# 2_main_mcu.net
KiCad netlist of a schematic drawn in Altium Designer
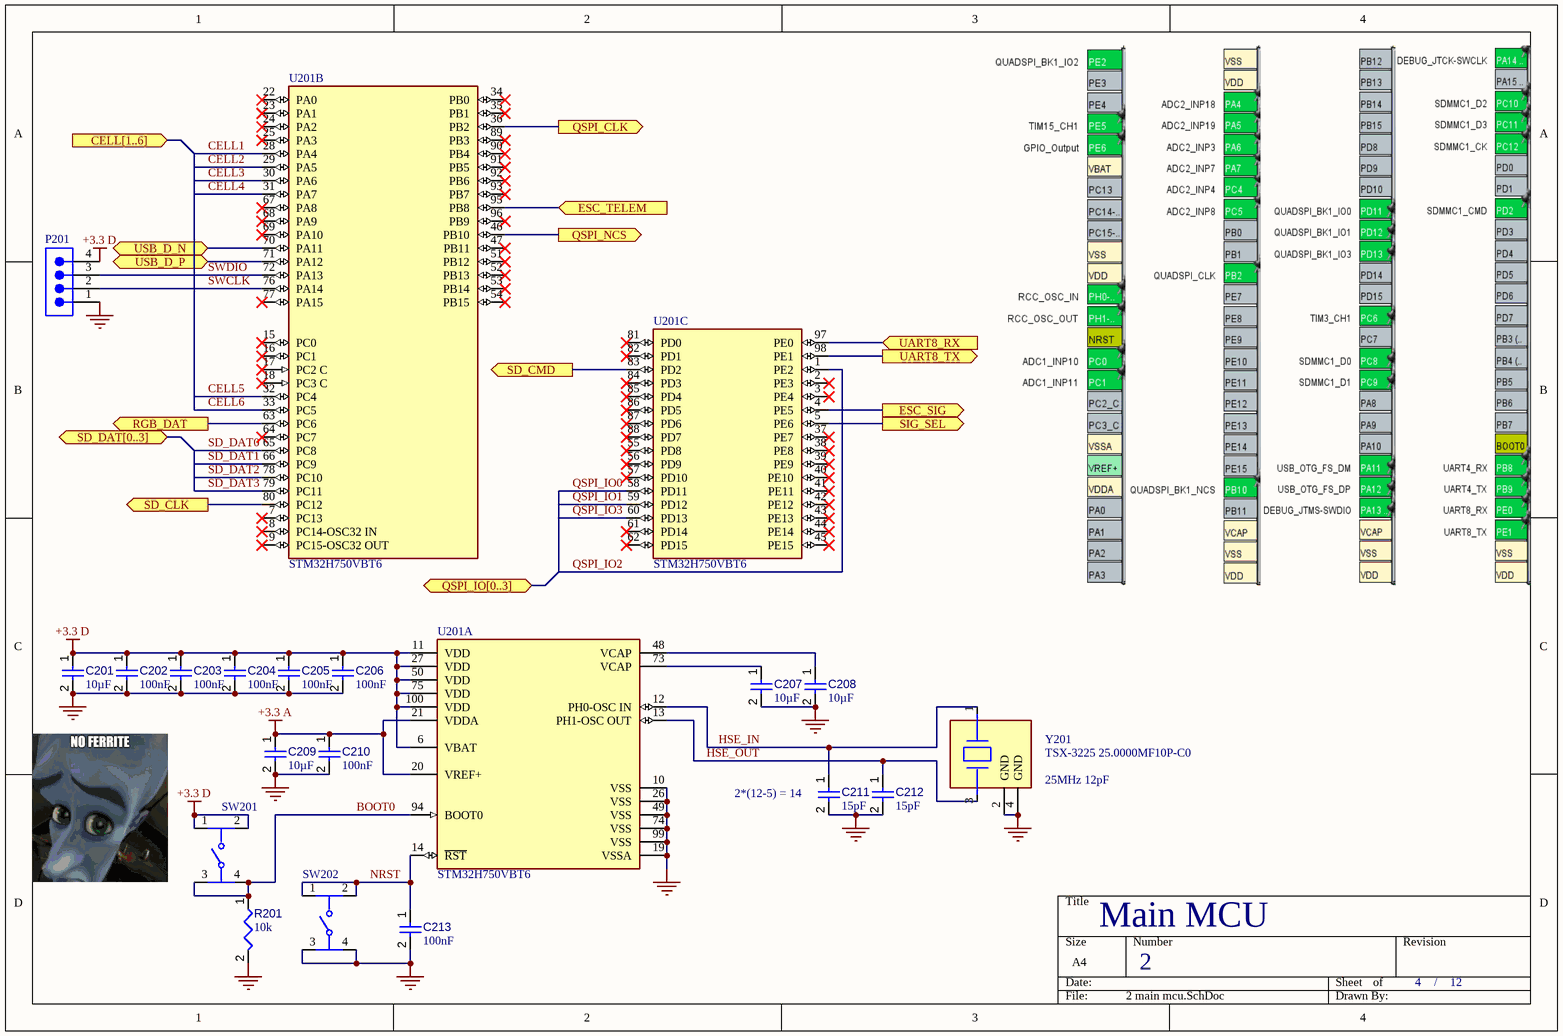
[diagram p0: 2 main mcu.SchDoc]

(export (version "E")
  (design (tool "Eeschema 10.0.6"))
  (components
    (comp (ref "C201")
      (value "10µF")
      (footprint "CAPC0603(1608)100_L")
      (description "Chip Capacitor, 10µF +/-20%, 10V, 0603, Thickness 1 mm")
      (fields (field (name "TOLERANCE") "10%") (field (name "Comment") "Capacitor 10µF +/-20% 10V 0603"))
      (libsource (lib "UBC Uncrewed Aircraft Systems") (part "CAP-NP-2"))
    )
    (comp (ref "C202")
      (value "100nF")
      (footprint "CAPC0402(1005)60_L")
      (description "Chip Capacitor, 100nF +/-20%, 25V, 0402, Thickness 0.6 mm")
      (fields (field (name "TOLERANCE") "10%") (field (name "Comment") "Capacitor 100nF +/-20% 25V 0402"))
      (libsource (lib "UBC Uncrewed Aircraft Systems") (part "CAP-NP-2"))
    )
    (comp (ref "C203")
      (value "100nF")
      (footprint "CAPC0402(1005)60_L")
      (description "Chip Capacitor, 100nF +/-20%, 25V, 0402, Thickness 0.6 mm")
      (fields (field (name "TOLERANCE") "10%") (field (name "Comment") "Capacitor 100nF +/-20% 25V 0402"))
      (libsource (lib "UBC Uncrewed Aircraft Systems") (part "CAP-NP-2"))
    )
    (comp (ref "C204")
      (value "100nF")
      (footprint "CAPC0402(1005)60_L")
      (description "Chip Capacitor, 100nF +/-20%, 25V, 0402, Thickness 0.6 mm")
      (fields (field (name "TOLERANCE") "10%") (field (name "Comment") "Capacitor 100nF +/-20% 25V 0402"))
      (libsource (lib "UBC Uncrewed Aircraft Systems") (part "CAP-NP-2"))
    )
    (comp (ref "C205")
      (value "100nF")
      (footprint "CAPC0402(1005)60_L")
      (description "Chip Capacitor, 100nF +/-20%, 25V, 0402, Thickness 0.6 mm")
      (fields (field (name "TOLERANCE") "10%") (field (name "Comment") "Capacitor 100nF +/-20% 25V 0402"))
      (libsource (lib "UBC Uncrewed Aircraft Systems") (part "CAP-NP-2"))
    )
    (comp (ref "C206")
      (value "100nF")
      (footprint "CAPC0402(1005)60_L")
      (description "Chip Capacitor, 100nF +/-20%, 25V, 0402, Thickness 0.6 mm")
      (fields (field (name "TOLERANCE") "10%") (field (name "Comment") "Capacitor 100nF +/-20% 25V 0402"))
      (libsource (lib "UBC Uncrewed Aircraft Systems") (part "CAP-NP-2"))
    )
    (comp (ref "C207")
      (value "10µF")
      (footprint "CAPC0603(1608)100_L")
      (description "Chip Capacitor, 10µF +/-20%, 10V, 0603, Thickness 1 mm")
      (fields (field (name "TOLERANCE") "10%") (field (name "Comment") "Capacitor 10µF +/-20% 10V 0603"))
      (libsource (lib "UBC Uncrewed Aircraft Systems") (part "CAP-NP-2"))
    )
    (comp (ref "C208")
      (value "10µF")
      (footprint "CAPC0603(1608)100_L")
      (description "Chip Capacitor, 10µF +/-20%, 10V, 0603, Thickness 1 mm")
      (fields (field (name "TOLERANCE") "10%") (field (name "Comment") "Capacitor 10µF +/-20% 10V 0603"))
      (libsource (lib "UBC Uncrewed Aircraft Systems") (part "CAP-NP-2"))
    )
    (comp (ref "C209")
      (value "10µF")
      (footprint "CAPC0603(1608)100_L")
      (description "Chip Capacitor, 10µF +/-20%, 10V, 0603, Thickness 1 mm")
      (fields (field (name "TOLERANCE") "10%") (field (name "Comment") "Capacitor 10µF +/-20% 10V 0603"))
      (libsource (lib "UBC Uncrewed Aircraft Systems") (part "CAP-NP-2"))
    )
    (comp (ref "C210")
      (value "100nF")
      (footprint "CAPC0402(1005)60_L")
      (description "Chip Capacitor, 100nF +/-20%, 25V, 0402, Thickness 0.6 mm")
      (fields (field (name "TOLERANCE") "10%") (field (name "Comment") "Capacitor 100nF +/-20% 25V 0402"))
      (libsource (lib "UBC Uncrewed Aircraft Systems") (part "CAP-NP-2"))
    )
    (comp (ref "C211")
      (value "15pF")
      (footprint "CAPC0402(1005)60_L")
      (description "Chip Capacitor, 15pF +/-20%, 50V, 0402, Thickness 0.6 mm")
      (fields (field (name "TOLERANCE") "5%") (field (name "JLCPCB PART #") "C1548"))
      (libsource (lib "UBC Uncrewed Aircraft Systems") (part "CAP-NP-2"))
    )
    (comp (ref "C212")
      (value "15pF")
      (footprint "CAPC0402(1005)60_L")
      (description "Chip Capacitor, 15pF +/-20%, 50V, 0402, Thickness 0.6 mm")
      (fields (field (name "TOLERANCE") "5%") (field (name "JLCPCB PART #") "C1548"))
      (libsource (lib "UBC Uncrewed Aircraft Systems") (part "CAP-NP-2"))
    )
    (comp (ref "C213")
      (value "100nF")
      (footprint "CAPC0402(1005)60_L")
      (description "Chip Capacitor, 100nF +/-20%, 25V, 0402, Thickness 0.6 mm")
      (fields (field (name "TOLERANCE") "10%") (field (name "Comment") "Capacitor 100nF +/-20% 25V 0402"))
      (libsource (lib "UBC Uncrewed Aircraft Systems") (part "CAP-NP-2"))
    )
    (comp (ref "P201")
      (value "61300411121")
      (footprint "61300411121")
      (libsource (lib "Altium Content Vault") (part "Header_Male_1R_04P"))
    )
    (comp (ref "R201")
      (value "10k")
      (footprint "RESC0402(1005)_L")
      (description "Chip Resistor, 10 kOhms, +/-1 %, 63 mW, -55 to 125 degC, 0402")
      (fields (field (name "POWER") "63mW") (field (name "TOLERANCE") "1%"))
      (libsource (lib "UBC Uncrewed Aircraft Systems") (part "RES-2"))
    )
    (comp (ref "SW201")
      (value "PTS810SJM250SMTRLFS")
      (footprint "FP-PTS810SJM250SMTRLFS-MFG")
      (description "SWITCH TACTILE SPST-NO 0.05A 16V")
      (libsource (lib "Altium Content Vault") (part "1adf0dd01260c80cf25a44bfd6b99ba"))
    )
    (comp (ref "SW202")
      (value "PTS810SJM250SMTRLFS")
      (footprint "FP-PTS810SJM250SMTRLFS-MFG")
      (description "SWITCH TACTILE SPST-NO 0.05A 16V")
      (libsource (lib "Altium Content Vault") (part "1adf0dd01260c80cf25a44bfd6b99ba"))
    )
    (comp (ref "U201")
      (value "STM32H750VBT6")
      (footprint "FP-LQFP100-1L-MFG")
      (description "IC MCU 32BIT 128KB FLASH 100LQFP")
      (fields
        (field (name "OCTOPART") "https://octopart.com/stm32h750vbt6-stmicroelectronics-94048547")
        (field (name "MANUFACTURER") "STMicroelectronics")
      )
      (libsource (lib "Altium Content Vault") (part "aca449acb2b80670ba40d015d68dc7a"))
    )
    (comp (ref "Y201")
      (value "TSX-3225 25.0000MF10P-C0")
      (footprint "FP-TSX-3225-MFG")
      (description "CRYSTAL 25.0000MHZ 18PF SMD")
      (libsource (lib "Altium Content Vault") (part "927a1cf76fcef45674bd853ccf050d4"))
    )
  )
  (nets
    (net (code "1") (name "+3.3 A") (class "Default")
      (node (ref "C209") (pin "1") (pinfunction "1_1") (pintype "passive"))
      (node (ref "C210") (pin "1") (pinfunction "1_1") (pintype "passive"))
      (node (ref "U201") (pin "20") (pinfunction "VREF+_20") (pintype "power_in"))
      (node (ref "U201") (pin "21") (pinfunction "VDDA_21") (pintype "power_in"))
    )
    (net (code "2") (name "+3.3 D") (class "Default")
      (node (ref "C201") (pin "1") (pinfunction "1_1") (pintype "passive"))
      (node (ref "C202") (pin "1") (pinfunction "1_1") (pintype "passive"))
      (node (ref "C203") (pin "1") (pinfunction "1_1") (pintype "passive"))
      (node (ref "C204") (pin "1") (pinfunction "1_1") (pintype "passive"))
      (node (ref "C205") (pin "1") (pinfunction "1_1") (pintype "passive"))
      (node (ref "C206") (pin "1") (pinfunction "1_1") (pintype "passive"))
      (node (ref "P201") (pin "4") (pinfunction "4_4") (pintype "passive"))
      (node (ref "SW201") (pin "1") (pinfunction "1_1") (pintype "passive"))
      (node (ref "SW201") (pin "2") (pinfunction "2_2") (pintype "passive"))
      (node (ref "U201") (pin "100") (pinfunction "VDD_100") (pintype "power_in"))
      (node (ref "U201") (pin "11") (pinfunction "VDD_11") (pintype "power_in"))
      (node (ref "U201") (pin "27") (pinfunction "VDD_27") (pintype "power_in"))
      (node (ref "U201") (pin "50") (pinfunction "VDD_50") (pintype "power_in"))
      (node (ref "U201") (pin "6") (pinfunction "VBAT_6") (pintype "power_in"))
      (node (ref "U201") (pin "75") (pinfunction "VDD_75") (pintype "power_in"))
    )
    (net (code "3") (name "/BOOT0") (class "Default")
      (node (ref "R201") (pin "1") (pinfunction "1_1") (pintype "passive"))
      (node (ref "SW201") (pin "3") (pinfunction "3_3") (pintype "passive"))
      (node (ref "SW201") (pin "4") (pinfunction "4_4") (pintype "passive"))
      (node (ref "U201") (pin "94") (pinfunction "BOOT0_94") (pintype "input"))
    )
    (net (code "4") (name "/CELL1") (class "Default")
      (node (ref "U201") (pin "28") (pinfunction "PA4_28") (pintype "bidirectional"))
    )
    (net (code "5") (name "/CELL2") (class "Default")
      (node (ref "U201") (pin "29") (pinfunction "PA5_29") (pintype "bidirectional"))
    )
    (net (code "6") (name "/CELL3") (class "Default")
      (node (ref "U201") (pin "30") (pinfunction "PA6_30") (pintype "bidirectional"))
    )
    (net (code "7") (name "/CELL4") (class "Default")
      (node (ref "U201") (pin "31") (pinfunction "PA7_31") (pintype "bidirectional"))
    )
    (net (code "8") (name "/CELL5") (class "Default")
      (node (ref "U201") (pin "32") (pinfunction "PC4_32") (pintype "bidirectional"))
    )
    (net (code "9") (name "/CELL6") (class "Default")
      (node (ref "U201") (pin "33") (pinfunction "PC5_33") (pintype "bidirectional"))
    )
    (net (code "11") (name "/ESC_SIG") (class "Default")
      (node (ref "U201") (pin "4") (pinfunction "PE5_4") (pintype "bidirectional"))
    )
    (net (code "12") (name "/ESC_TELEM") (class "Default")
      (node (ref "U201") (pin "95") (pinfunction "PB8_95") (pintype "bidirectional"))
    )
    (net (code "13") (name "/HSE_IN") (class "Default")
      (node (ref "C211") (pin "1") (pinfunction "1_1") (pintype "passive"))
      (node (ref "U201") (pin "12") (pinfunction "PH0-OSC_IN_12") (pintype "bidirectional"))
      (node (ref "Y201") (pin "1") (pinfunction "1_1") (pintype "passive"))
    )
    (net (code "14") (name "/HSE_OUT") (class "Default")
      (node (ref "C212") (pin "1") (pinfunction "1_1") (pintype "passive"))
      (node (ref "U201") (pin "13") (pinfunction "PH1-OSC_OUT_13") (pintype "bidirectional"))
      (node (ref "Y201") (pin "3") (pinfunction "3_3") (pintype "passive"))
    )
    (net (code "15") (name "/NRST") (class "Default")
      (node (ref "C213") (pin "1") (pinfunction "1_1") (pintype "passive"))
      (node (ref "SW202") (pin "1") (pinfunction "1_1") (pintype "passive"))
      (node (ref "SW202") (pin "2") (pinfunction "2_2") (pintype "passive"))
      (node (ref "U201") (pin "14") (pinfunction "~{RST}_14") (pintype "bidirectional"))
    )
    (net (code "16") (name "/QSPI_CLK") (class "Default")
      (node (ref "U201") (pin "36") (pinfunction "PB2_36") (pintype "bidirectional"))
    )
    (net (code "17") (name "/QSPI_IO0") (class "Default")
      (node (ref "U201") (pin "58") (pinfunction "PD11_58") (pintype "bidirectional"))
    )
    (net (code "18") (name "/QSPI_IO1") (class "Default")
      (node (ref "U201") (pin "59") (pinfunction "PD12_59") (pintype "bidirectional"))
    )
    (net (code "19") (name "/QSPI_IO2") (class "Default")
      (node (ref "U201") (pin "1") (pinfunction "PE2_1") (pintype "bidirectional"))
    )
    (net (code "20") (name "/QSPI_IO3") (class "Default")
      (node (ref "U201") (pin "60") (pinfunction "PD13_60") (pintype "bidirectional"))
    )
    (net (code "22") (name "/QSPI_NCS") (class "Default")
      (node (ref "U201") (pin "46") (pinfunction "PB10_46") (pintype "bidirectional"))
    )
    (net (code "23") (name "/RGB_DAT") (class "Default")
      (node (ref "U201") (pin "63") (pinfunction "PC6_63") (pintype "bidirectional"))
    )
    (net (code "24") (name "/SD_CLK") (class "Default")
      (node (ref "U201") (pin "80") (pinfunction "PC12_80") (pintype "bidirectional"))
    )
    (net (code "25") (name "/SD_CMD") (class "Default")
      (node (ref "U201") (pin "83") (pinfunction "PD2_83") (pintype "bidirectional"))
    )
    (net (code "26") (name "/SD_DAT0") (class "Default")
      (node (ref "U201") (pin "65") (pinfunction "PC8_65") (pintype "bidirectional"))
    )
    (net (code "27") (name "/SD_DAT1") (class "Default")
      (node (ref "U201") (pin "66") (pinfunction "PC9_66") (pintype "bidirectional"))
    )
    (net (code "28") (name "/SD_DAT2") (class "Default")
      (node (ref "U201") (pin "78") (pinfunction "PC10_78") (pintype "bidirectional"))
    )
    (net (code "29") (name "/SD_DAT3") (class "Default")
      (node (ref "U201") (pin "79") (pinfunction "PC11_79") (pintype "bidirectional"))
    )
    (net (code "31") (name "/SIG_SEL") (class "Default")
      (node (ref "U201") (pin "5") (pinfunction "PE6_5") (pintype "bidirectional"))
    )
    (net (code "32") (name "/SWCLK") (class "Default")
      (node (ref "P201") (pin "2") (pinfunction "2_2") (pintype "passive"))
      (node (ref "U201") (pin "76") (pinfunction "PA14_76") (pintype "bidirectional"))
    )
    (net (code "33") (name "/SWDIO") (class "Default")
      (node (ref "P201") (pin "3") (pinfunction "3_3") (pintype "passive"))
      (node (ref "U201") (pin "72") (pinfunction "PA13_72") (pintype "bidirectional"))
    )
    (net (code "34") (name "/UART8_RX") (class "Default")
      (node (ref "U201") (pin "97") (pinfunction "PE0_97") (pintype "bidirectional"))
    )
    (net (code "35") (name "/UART8_TX") (class "Default")
      (node (ref "U201") (pin "98") (pinfunction "PE1_98") (pintype "bidirectional"))
    )
    (net (code "36") (name "/USB_D_N") (class "Default")
      (node (ref "U201") (pin "70") (pinfunction "PA11_70") (pintype "bidirectional"))
    )
    (net (code "37") (name "/USB_D_P") (class "Default")
      (node (ref "U201") (pin "71") (pinfunction "PA12_71") (pintype "bidirectional"))
    )
    (net (code "38") (name "GND") (class "Default")
      (node (ref "C201") (pin "2") (pinfunction "2_2") (pintype "passive"))
      (node (ref "C202") (pin "2") (pinfunction "2_2") (pintype "passive"))
      (node (ref "C203") (pin "2") (pinfunction "2_2") (pintype "passive"))
      (node (ref "C204") (pin "2") (pinfunction "2_2") (pintype "passive"))
      (node (ref "C205") (pin "2") (pinfunction "2_2") (pintype "passive"))
      (node (ref "C206") (pin "2") (pinfunction "2_2") (pintype "passive"))
      (node (ref "C207") (pin "2") (pinfunction "2_2") (pintype "passive"))
      (node (ref "C208") (pin "2") (pinfunction "2_2") (pintype "passive"))
      (node (ref "C209") (pin "2") (pinfunction "2_2") (pintype "passive"))
      (node (ref "C210") (pin "2") (pinfunction "2_2") (pintype "passive"))
      (node (ref "C211") (pin "2") (pinfunction "2_2") (pintype "passive"))
      (node (ref "C212") (pin "2") (pinfunction "2_2") (pintype "passive"))
      (node (ref "C213") (pin "2") (pinfunction "2_2") (pintype "passive"))
      (node (ref "P201") (pin "1") (pinfunction "1_1") (pintype "passive"))
      (node (ref "R201") (pin "2") (pinfunction "2_2") (pintype "passive"))
      (node (ref "SW202") (pin "3") (pinfunction "3_3") (pintype "passive"))
      (node (ref "SW202") (pin "4") (pinfunction "4_4") (pintype "passive"))
      (node (ref "U201") (pin "10") (pinfunction "VSS_10") (pintype "power_in"))
      (node (ref "U201") (pin "19") (pinfunction "VSSA_19") (pintype "power_in"))
      (node (ref "U201") (pin "26") (pinfunction "VSS_26") (pintype "power_in"))
      (node (ref "U201") (pin "49") (pinfunction "VSS_49") (pintype "power_in"))
      (node (ref "U201") (pin "74") (pinfunction "VSS_74") (pintype "power_in"))
      (node (ref "U201") (pin "99") (pinfunction "VSS_99") (pintype "power_in"))
      (node (ref "Y201") (pin "2") (pinfunction "GND_2") (pintype "power_in"))
      (node (ref "Y201") (pin "4") (pinfunction "GND_4") (pintype "power_in"))
    )
    (net (code "39") (name "Net-(C207-Pad1)") (class "Default")
      (node (ref "C207") (pin "1") (pinfunction "1_1") (pintype "passive"))
      (node (ref "U201") (pin "73") (pinfunction "VCAP_73") (pintype "power_in"))
    )
    (net (code "40") (name "Net-(C208-Pad1)") (class "Default")
      (node (ref "C208") (pin "1") (pinfunction "1_1") (pintype "passive"))
      (node (ref "U201") (pin "48") (pinfunction "VCAP_48") (pintype "power_in"))
    )
    (net (code "41") (name "unconnected-(U201B-PA0-Pad22)") (class "Default")
      (node (ref "U201") (pin "22") (pinfunction "PA0_22") (pintype "bidirectional+no_connect"))
    )
    (net (code "42") (name "unconnected-(U201B-PA1-Pad23)") (class "Default")
      (node (ref "U201") (pin "23") (pinfunction "PA1_23") (pintype "bidirectional+no_connect"))
    )
    (net (code "43") (name "unconnected-(U201B-PA2-Pad24)") (class "Default")
      (node (ref "U201") (pin "24") (pinfunction "PA2_24") (pintype "bidirectional+no_connect"))
    )
    (net (code "44") (name "unconnected-(U201B-PA3-Pad25)") (class "Default")
      (node (ref "U201") (pin "25") (pinfunction "PA3_25") (pintype "bidirectional+no_connect"))
    )
    (net (code "45") (name "unconnected-(U201B-PA8-Pad67)") (class "Default")
      (node (ref "U201") (pin "67") (pinfunction "PA8_67") (pintype "bidirectional+no_connect"))
    )
    (net (code "46") (name "unconnected-(U201B-PA9-Pad68)") (class "Default")
      (node (ref "U201") (pin "68") (pinfunction "PA9_68") (pintype "bidirectional+no_connect"))
    )
    (net (code "47") (name "unconnected-(U201B-PA10-Pad69)") (class "Default")
      (node (ref "U201") (pin "69") (pinfunction "PA10_69") (pintype "bidirectional+no_connect"))
    )
    (net (code "48") (name "unconnected-(U201B-PA15-Pad77)") (class "Default")
      (node (ref "U201") (pin "77") (pinfunction "PA15_77") (pintype "bidirectional+no_connect"))
    )
    (net (code "49") (name "unconnected-(U201B-PB0-Pad34)") (class "Default")
      (node (ref "U201") (pin "34") (pinfunction "PB0_34") (pintype "bidirectional+no_connect"))
    )
    (net (code "50") (name "unconnected-(U201B-PB1-Pad35)") (class "Default")
      (node (ref "U201") (pin "35") (pinfunction "PB1_35") (pintype "bidirectional+no_connect"))
    )
    (net (code "51") (name "unconnected-(U201B-PB3-Pad89)") (class "Default")
      (node (ref "U201") (pin "89") (pinfunction "PB3_89") (pintype "bidirectional+no_connect"))
    )
    (net (code "52") (name "unconnected-(U201B-PB4-Pad90)") (class "Default")
      (node (ref "U201") (pin "90") (pinfunction "PB4_90") (pintype "bidirectional+no_connect"))
    )
    (net (code "53") (name "unconnected-(U201B-PB5-Pad91)") (class "Default")
      (node (ref "U201") (pin "91") (pinfunction "PB5_91") (pintype "bidirectional+no_connect"))
    )
    (net (code "54") (name "unconnected-(U201B-PB6-Pad92)") (class "Default")
      (node (ref "U201") (pin "92") (pinfunction "PB6_92") (pintype "bidirectional+no_connect"))
    )
    (net (code "55") (name "unconnected-(U201B-PB7-Pad93)") (class "Default")
      (node (ref "U201") (pin "93") (pinfunction "PB7_93") (pintype "bidirectional+no_connect"))
    )
    (net (code "56") (name "unconnected-(U201B-PB9-Pad96)") (class "Default")
      (node (ref "U201") (pin "96") (pinfunction "PB9_96") (pintype "bidirectional+no_connect"))
    )
    (net (code "57") (name "unconnected-(U201B-PB11-Pad47)") (class "Default")
      (node (ref "U201") (pin "47") (pinfunction "PB11_47") (pintype "bidirectional+no_connect"))
    )
    (net (code "58") (name "unconnected-(U201B-PB12-Pad51)") (class "Default")
      (node (ref "U201") (pin "51") (pinfunction "PB12_51") (pintype "bidirectional+no_connect"))
    )
    (net (code "59") (name "unconnected-(U201B-PB13-Pad52)") (class "Default")
      (node (ref "U201") (pin "52") (pinfunction "PB13_52") (pintype "bidirectional+no_connect"))
    )
    (net (code "60") (name "unconnected-(U201B-PB14-Pad53)") (class "Default")
      (node (ref "U201") (pin "53") (pinfunction "PB14_53") (pintype "bidirectional+no_connect"))
    )
    (net (code "61") (name "unconnected-(U201B-PB15-Pad54)") (class "Default")
      (node (ref "U201") (pin "54") (pinfunction "PB15_54") (pintype "bidirectional+no_connect"))
    )
    (net (code "62") (name "unconnected-(U201B-PC0-Pad15)") (class "Default")
      (node (ref "U201") (pin "15") (pinfunction "PC0_15") (pintype "bidirectional+no_connect"))
    )
    (net (code "63") (name "unconnected-(U201B-PC1-Pad16)") (class "Default")
      (node (ref "U201") (pin "16") (pinfunction "PC1_16") (pintype "bidirectional+no_connect"))
    )
    (net (code "64") (name "unconnected-(U201B-PC2_C-Pad17)") (class "Default")
      (node (ref "U201") (pin "17") (pinfunction "PC2_C_17") (pintype "input+no_connect"))
    )
    (net (code "65") (name "unconnected-(U201B-PC3_C-Pad18)") (class "Default")
      (node (ref "U201") (pin "18") (pinfunction "PC3_C_18") (pintype "input+no_connect"))
    )
    (net (code "66") (name "unconnected-(U201B-PC7-Pad64)") (class "Default")
      (node (ref "U201") (pin "64") (pinfunction "PC7_64") (pintype "bidirectional+no_connect"))
    )
    (net (code "67") (name "unconnected-(U201B-PC13-Pad7)") (class "Default")
      (node (ref "U201") (pin "7") (pinfunction "PC13_7") (pintype "bidirectional+no_connect"))
    )
    (net (code "68") (name "unconnected-(U201B-PC14-OSC32_IN-Pad8)") (class "Default")
      (node (ref "U201") (pin "8") (pinfunction "PC14-OSC32_IN_8") (pintype "bidirectional+no_connect"))
    )
    (net (code "69") (name "unconnected-(U201B-PC15-OSC32_OUT-Pad9)") (class "Default")
      (node (ref "U201") (pin "9") (pinfunction "PC15-OSC32_OUT_9") (pintype "bidirectional+no_connect"))
    )
    (net (code "70") (name "unconnected-(U201C-PD0-Pad81)") (class "Default")
      (node (ref "U201") (pin "81") (pinfunction "PD0_81") (pintype "bidirectional+no_connect"))
    )
    (net (code "71") (name "unconnected-(U201C-PD1-Pad82)") (class "Default")
      (node (ref "U201") (pin "82") (pinfunction "PD1_82") (pintype "bidirectional+no_connect"))
    )
    (net (code "72") (name "unconnected-(U201C-PD3-Pad84)") (class "Default")
      (node (ref "U201") (pin "84") (pinfunction "PD3_84") (pintype "bidirectional+no_connect"))
    )
    (net (code "73") (name "unconnected-(U201C-PD4-Pad85)") (class "Default")
      (node (ref "U201") (pin "85") (pinfunction "PD4_85") (pintype "bidirectional+no_connect"))
    )
    (net (code "74") (name "unconnected-(U201C-PD5-Pad86)") (class "Default")
      (node (ref "U201") (pin "86") (pinfunction "PD5_86") (pintype "bidirectional+no_connect"))
    )
    (net (code "75") (name "unconnected-(U201C-PD6-Pad87)") (class "Default")
      (node (ref "U201") (pin "87") (pinfunction "PD6_87") (pintype "bidirectional+no_connect"))
    )
    (net (code "76") (name "unconnected-(U201C-PD7-Pad88)") (class "Default")
      (node (ref "U201") (pin "88") (pinfunction "PD7_88") (pintype "bidirectional+no_connect"))
    )
    (net (code "77") (name "unconnected-(U201C-PD8-Pad55)") (class "Default")
      (node (ref "U201") (pin "55") (pinfunction "PD8_55") (pintype "bidirectional+no_connect"))
    )
    (net (code "78") (name "unconnected-(U201C-PD9-Pad56)") (class "Default")
      (node (ref "U201") (pin "56") (pinfunction "PD9_56") (pintype "bidirectional+no_connect"))
    )
    (net (code "79") (name "unconnected-(U201C-PD10-Pad57)") (class "Default")
      (node (ref "U201") (pin "57") (pinfunction "PD10_57") (pintype "bidirectional+no_connect"))
    )
    (net (code "80") (name "unconnected-(U201C-PD14-Pad61)") (class "Default")
      (node (ref "U201") (pin "61") (pinfunction "PD14_61") (pintype "bidirectional+no_connect"))
    )
    (net (code "81") (name "unconnected-(U201C-PD15-Pad62)") (class "Default")
      (node (ref "U201") (pin "62") (pinfunction "PD15_62") (pintype "bidirectional+no_connect"))
    )
    (net (code "82") (name "unconnected-(U201C-PE3-Pad2)") (class "Default")
      (node (ref "U201") (pin "2") (pinfunction "PE3_2") (pintype "bidirectional+no_connect"))
    )
    (net (code "83") (name "unconnected-(U201C-PE4-Pad3)") (class "Default")
      (node (ref "U201") (pin "3") (pinfunction "PE4_3") (pintype "bidirectional+no_connect"))
    )
    (net (code "84") (name "unconnected-(U201C-PE7-Pad37)") (class "Default")
      (node (ref "U201") (pin "37") (pinfunction "PE7_37") (pintype "bidirectional+no_connect"))
    )
    (net (code "85") (name "unconnected-(U201C-PE8-Pad38)") (class "Default")
      (node (ref "U201") (pin "38") (pinfunction "PE8_38") (pintype "bidirectional+no_connect"))
    )
    (net (code "86") (name "unconnected-(U201C-PE9-Pad39)") (class "Default")
      (node (ref "U201") (pin "39") (pinfunction "PE9_39") (pintype "bidirectional+no_connect"))
    )
    (net (code "87") (name "unconnected-(U201C-PE10-Pad40)") (class "Default")
      (node (ref "U201") (pin "40") (pinfunction "PE10_40") (pintype "bidirectional+no_connect"))
    )
    (net (code "88") (name "unconnected-(U201C-PE11-Pad41)") (class "Default")
      (node (ref "U201") (pin "41") (pinfunction "PE11_41") (pintype "bidirectional+no_connect"))
    )
    (net (code "89") (name "unconnected-(U201C-PE12-Pad42)") (class "Default")
      (node (ref "U201") (pin "42") (pinfunction "PE12_42") (pintype "bidirectional+no_connect"))
    )
    (net (code "90") (name "unconnected-(U201C-PE13-Pad43)") (class "Default")
      (node (ref "U201") (pin "43") (pinfunction "PE13_43") (pintype "bidirectional+no_connect"))
    )
    (net (code "91") (name "unconnected-(U201C-PE14-Pad44)") (class "Default")
      (node (ref "U201") (pin "44") (pinfunction "PE14_44") (pintype "bidirectional+no_connect"))
    )
    (net (code "92") (name "unconnected-(U201C-PE15-Pad45)") (class "Default")
      (node (ref "U201") (pin "45") (pinfunction "PE15_45") (pintype "bidirectional+no_connect"))
    )
  )
)
